# The_ghostLink_schematic.net
KiCad netlist of a schematic drawn in EasyEDA
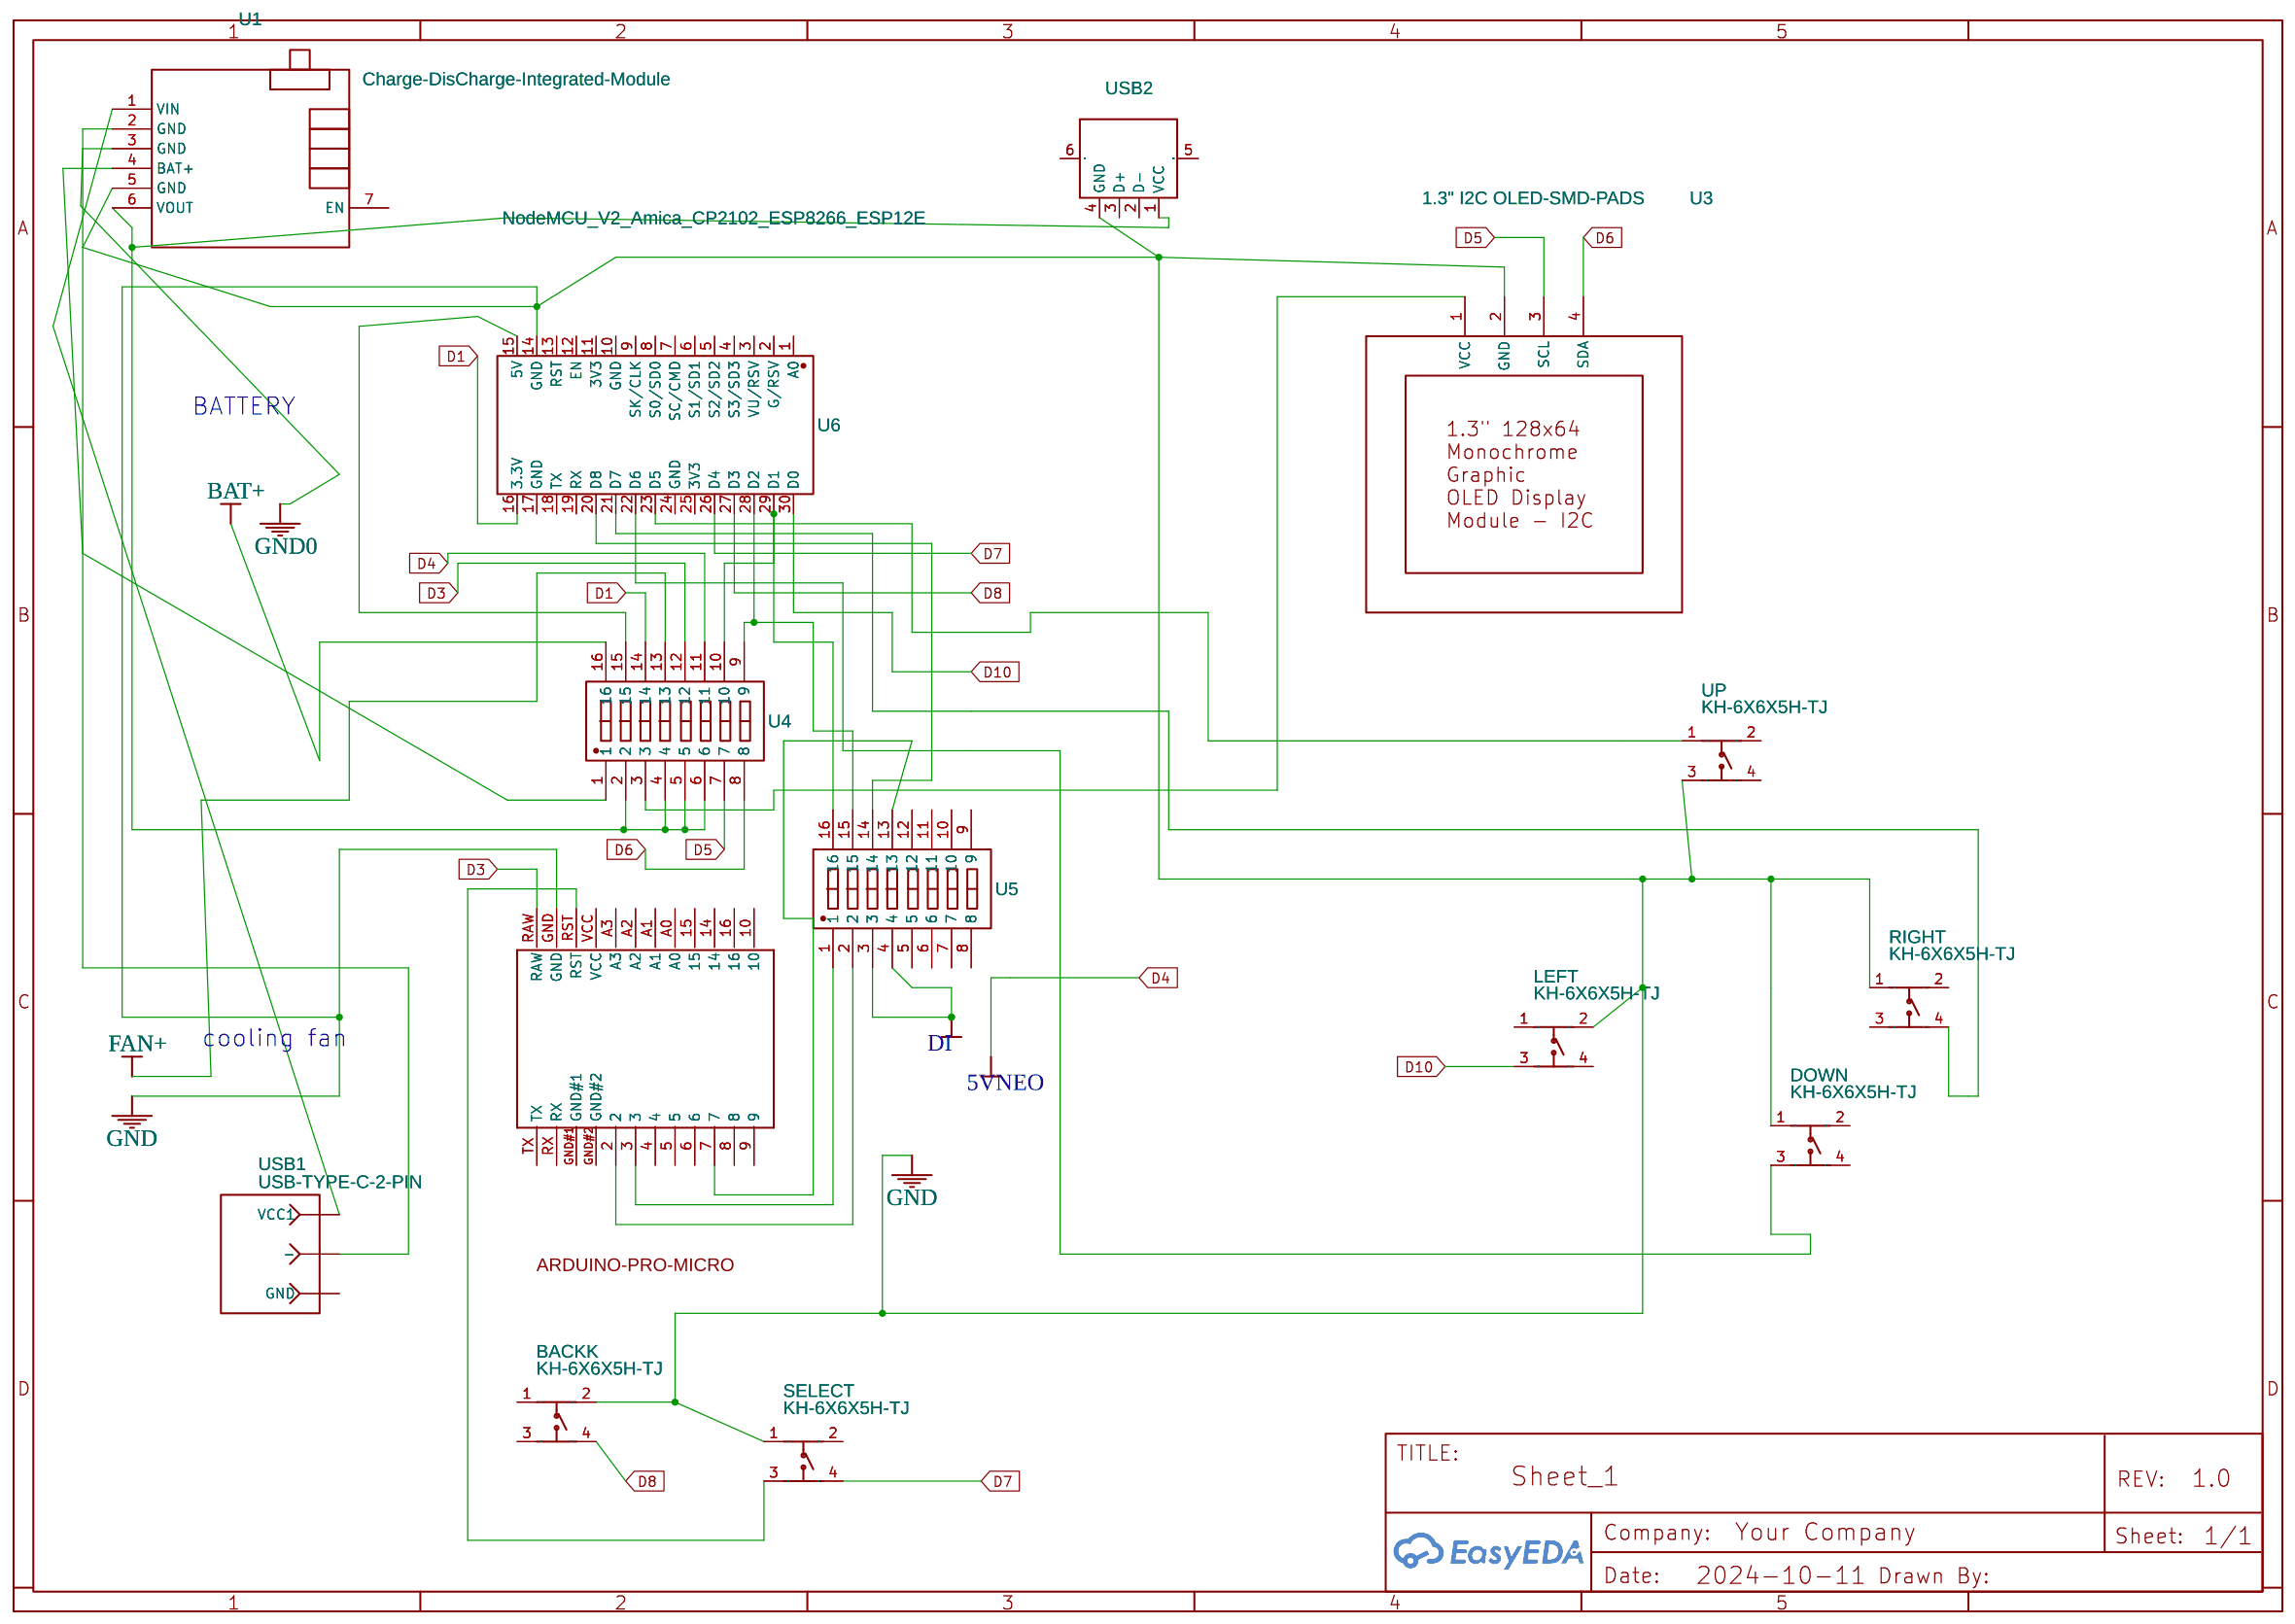
[diagram p0: schematic sheet]

(export (version "E")
  (design (tool "Eeschema 10.0.6"))
  (components
    (comp (ref "BACKK")
      (value "KH-6X6X5H-TJ")
      (fields (field (name "Manufacturer") "kinghelm(金航标)"))
      (libsource (lib "") (part "KH-6X6X5H-TJ_2"))
    )
    (comp (ref "DOWN")
      (value "KH-6X6X5H-TJ")
      (fields (field (name "Manufacturer") "kinghelm(金航标)"))
      (libsource (lib "") (part "KH-6X6X5H-TJ_1"))
    )
    (comp (ref "LEFT")
      (value "KH-6X6X5H-TJ")
      (fields (field (name "Manufacturer") "kinghelm(金航标)"))
      (libsource (lib "") (part "KH-6X6X5H-TJ"))
    )
    (comp (ref "RIGHT")
      (value "KH-6X6X5H-TJ")
      (fields (field (name "Manufacturer") "kinghelm(金航标)"))
      (libsource (lib "") (part "KH-6X6X5H-TJ_3"))
    )
    (comp (ref "SELECT")
      (value "KH-6X6X5H-TJ")
      (fields (field (name "Manufacturer") "kinghelm(金航标)"))
      (libsource (lib "") (part "KH-6X6X5H-TJ_4"))
    )
    (comp (ref "U1")
      (value "Charge-DisCharge-Integrated-Module")
      (libsource (lib "") (part "Charge-DisCharge-Integrated-Module"))
    )
    (comp (ref "U2") (value "ARDUINO PRO MICRO") (libsource (lib "") (part "ARDUINO PRO MICRO")))
    (comp (ref "U3")
      (value "1.3\" I2C OLED-SMD-PADS")
      (libsource (lib "") (part "1.3{dblquote} I2C OLED-SMD-PADS"))
    )
    (comp (ref "U4")
      (value "SMQS-08R-TP")
      (fields (field (name "Manufacturer") "SM Switch"))
      (libsource (lib "") (part "SMQS-08R-TP"))
    )
    (comp (ref "U5")
      (value "SMQS-08R-TP")
      (fields (field (name "Manufacturer") "SM Switch"))
      (libsource (lib "") (part "SMQS-08R-TP"))
    )
    (comp (ref "U6")
      (value "NodeMCU_V2_Amica_CP2102_ESP8266_ESP12E")
      (libsource (lib "") (part "NodeMCU_V2_Amica_CP2102_ESP8266_ESP12E"))
    )
    (comp (ref "UP")
      (value "KH-6X6X5H-TJ")
      (fields (field (name "Manufacturer") "kinghelm(金航标)"))
      (libsource (lib "") (part "KH-6X6X5H-TJ_5"))
    )
    (comp (ref "USB1") (value "USB-TYPE-C-2-PIN") (libsource (lib "") (part "USB-TYPE-C-2-PIN")))
    (comp (ref "USB2")
      (value "AF Bend foot Have side Inside the bomb iron PBT White plastic 90degree")
      (fields (field (name "Manufacturer Part") "901-131A1011D10100") (field (name "Manufacturer") "精拓金"))
      (libsource (lib "") (part "AF Bend foot Have side Inside the bomb iron PBT White plastic 90degree"))
    )
  )
  (nets
    (net (code "1") (name "BAT+") (class "Default")
      (node (ref "U4") (pin "16") (pinfunction "16_16") (pintype "unspecified"))
    )
    (net (code "2") (name "D1") (class "Default")
      (node (ref "U4") (pin "14") (pinfunction "14_14") (pintype "unspecified"))
      (node (ref "U6") (pin "16") (pinfunction "3.3V_16") (pintype "unspecified"))
    )
    (net (code "3") (name "D3") (class "Default")
      (node (ref "U2") (pin "RAW") (pinfunction "RAW_RAW") (pintype "bidirectional"))
      (node (ref "U4") (pin "12") (pinfunction "12_12") (pintype "unspecified"))
    )
    (net (code "4") (name "D4") (class "Default")
      (node (ref "U4") (pin "11") (pinfunction "11_11") (pintype "unspecified"))
    )
    (net (code "5") (name "D5") (class "Default")
      (node (ref "U3") (pin "3") (pinfunction "SCL_3") (pintype "unspecified"))
      (node (ref "U4") (pin "7") (pinfunction "7_7") (pintype "unspecified"))
    )
    (net (code "6") (name "D6") (class "Default")
      (node (ref "U3") (pin "4") (pinfunction "SDA_4") (pintype "unspecified"))
      (node (ref "U4") (pin "8") (pinfunction "8_8") (pintype "unspecified"))
    )
    (net (code "7") (name "D7") (class "Default")
      (node (ref "SELECT") (pin "4") (pinfunction "4_4") (pintype "unspecified"))
      (node (ref "U6") (pin "26") (pinfunction "D4_26") (pintype "unspecified"))
    )
    (net (code "8") (name "D8") (class "Default")
      (node (ref "BACKK") (pin "4") (pinfunction "4_4") (pintype "unspecified"))
      (node (ref "U6") (pin "27") (pinfunction "D3_27") (pintype "unspecified"))
    )
    (net (code "9") (name "D10") (class "Default")
      (node (ref "LEFT") (pin "3") (pinfunction "3_3") (pintype "unspecified"))
      (node (ref "U6") (pin "30") (pinfunction "D0_30") (pintype "unspecified"))
    )
    (net (code "10") (name "DI") (class "Default")
      (node (ref "U5") (pin "3") (pinfunction "3_3") (pintype "unspecified"))
      (node (ref "U5") (pin "4") (pinfunction "4_4") (pintype "unspecified"))
    )
    (net (code "11") (name "FAN+") (class "Default")
      (node (ref "U4") (pin "13") (pinfunction "13_13") (pintype "unspecified"))
    )
    (net (code "12") (name "GND") (class "Default")
      (node (ref "BACKK") (pin "2") (pinfunction "2_2") (pintype "unspecified"))
      (node (ref "DOWN") (pin "1") (pinfunction "1_1") (pintype "unspecified"))
      (node (ref "LEFT") (pin "2") (pinfunction "2_2") (pintype "unspecified"))
      (node (ref "RIGHT") (pin "1") (pinfunction "1_1") (pintype "unspecified"))
      (node (ref "SELECT") (pin "1") (pinfunction "1_1") (pintype "unspecified"))
      (node (ref "U1") (pin "5") (pinfunction "GND_5") (pintype "unspecified"))
      (node (ref "U2") (pin "GND") (pinfunction "GND_GND") (pintype "bidirectional"))
      (node (ref "U3") (pin "2") (pinfunction "GND_2") (pintype "unspecified"))
      (node (ref "U6") (pin "14") (pinfunction "GND_14") (pintype "unspecified"))
      (node (ref "UP") (pin "3") (pinfunction "3_3") (pintype "unspecified"))
      (node (ref "USB2") (pin "4") (pinfunction "GND_4") (pintype "input"))
    )
    (net (code "13") (name "GND0") (class "Default")
      (node (ref "U1") (pin "3") (pinfunction "GND_3") (pintype "unspecified"))
    )
    (net (code "14") (name "Net-(SELECT-Pad3)") (class "Default")
      (node (ref "SELECT") (pin "3") (pinfunction "3_3") (pintype "unspecified"))
      (node (ref "U2") (pin "RST") (pinfunction "RST_RST") (pintype "bidirectional"))
    )
    (net (code "15") (name "Net-(U1-BAT+)") (class "Default")
      (node (ref "U1") (pin "4") (pinfunction "BAT+_4") (pintype "unspecified"))
      (node (ref "U4") (pin "1") (pinfunction "1_1") (pintype "unspecified"))
    )
    (net (code "16") (name "Net-(U1-VIN)") (class "Default")
      (node (ref "U1") (pin "1") (pinfunction "VIN_1") (pintype "unspecified"))
      (node (ref "USB1") (pin "1") (pinfunction "VCC1_1") (pintype "unspecified"))
    )
    (net (code "17") (name "Net-(U1-VOUT)") (class "Default")
      (node (ref "U1") (pin "6") (pinfunction "VOUT_6") (pintype "unspecified"))
      (node (ref "U4") (pin "2") (pinfunction "2_2") (pintype "unspecified"))
      (node (ref "U4") (pin "4") (pinfunction "4_4") (pintype "unspecified"))
      (node (ref "U4") (pin "5") (pinfunction "5_5") (pintype "unspecified"))
      (node (ref "U4") (pin "6") (pinfunction "6_6") (pintype "unspecified"))
      (node (ref "USB2") (pin "1") (pinfunction "VCC_1") (pintype "input"))
    )
    (net (code "18") (name "Net-(U2-Pad2)") (class "Default")
      (node (ref "U2") (pin "2") (pinfunction "2_2") (pintype "bidirectional"))
      (node (ref "U5") (pin "2") (pinfunction "2_2") (pintype "unspecified"))
    )
    (net (code "19") (name "Net-(U2-Pad3)") (class "Default")
      (node (ref "U2") (pin "3") (pinfunction "3_3") (pintype "bidirectional"))
      (node (ref "U5") (pin "1") (pinfunction "1_1") (pintype "unspecified"))
    )
    (net (code "20") (name "Net-(U2-Pad7)") (class "Default")
      (node (ref "U2") (pin "7") (pinfunction "7_7") (pintype "bidirectional"))
      (node (ref "U5") (pin "13") (pinfunction "13_13") (pintype "unspecified"))
    )
    (net (code "21") (name "Net-(U3-VCC)") (class "Default")
      (node (ref "U3") (pin "1") (pinfunction "VCC_1") (pintype "unspecified"))
      (node (ref "U4") (pin "3") (pinfunction "3_3") (pintype "unspecified"))
    )
    (net (code "22") (name "Net-(U6-5V)") (class "Default")
      (node (ref "U4") (pin "15") (pinfunction "15_15") (pintype "unspecified"))
      (node (ref "U6") (pin "15") (pinfunction "5V_15") (pintype "unspecified"))
    )
    (net (code "23") (name "Net-(U6-D1)") (class "Default")
      (node (ref "U4") (pin "10") (pinfunction "10_10") (pintype "unspecified"))
      (node (ref "U5") (pin "16") (pinfunction "16_16") (pintype "unspecified"))
      (node (ref "U6") (pin "29") (pinfunction "D1_29") (pintype "unspecified"))
    )
    (net (code "24") (name "Net-(U6-D2)") (class "Default")
      (node (ref "U4") (pin "9") (pinfunction "9_9") (pintype "unspecified"))
      (node (ref "U5") (pin "15") (pinfunction "15_15") (pintype "unspecified"))
      (node (ref "U6") (pin "28") (pinfunction "D2_28") (pintype "unspecified"))
    )
    (net (code "25") (name "Net-(U6-D5)") (class "Default")
      (node (ref "U6") (pin "23") (pinfunction "D5_23") (pintype "unspecified"))
      (node (ref "UP") (pin "1") (pinfunction "1_1") (pintype "unspecified"))
    )
    (net (code "26") (name "Net-(U6-D6)") (class "Default")
      (node (ref "DOWN") (pin "3") (pinfunction "3_3") (pintype "unspecified"))
      (node (ref "U6") (pin "22") (pinfunction "D6_22") (pintype "unspecified"))
    )
    (net (code "27") (name "Net-(U6-D7)") (class "Default")
      (node (ref "RIGHT") (pin "4") (pinfunction "4_4") (pintype "unspecified"))
      (node (ref "U6") (pin "21") (pinfunction "D7_21") (pintype "unspecified"))
    )
    (net (code "28") (name "Net-(U6-D8)") (class "Default")
      (node (ref "U5") (pin "14") (pinfunction "14_14") (pintype "unspecified"))
      (node (ref "U6") (pin "20") (pinfunction "D8_20") (pintype "unspecified"))
    )
    (net (code "29") (name "Net-(USB1--)") (class "Default")
      (node (ref "U1") (pin "2") (pinfunction "GND_2") (pintype "unspecified"))
      (node (ref "USB1") (pin "2") (pinfunction "-_2") (pintype "unspecified"))
    )
    (net (code "30") (name "unconnected-(BACKK-Pad1)") (class "Default")
      (node (ref "BACKK") (pin "1") (pinfunction "1_1") (pintype "unspecified"))
    )
    (net (code "31") (name "unconnected-(BACKK-Pad3)") (class "Default")
      (node (ref "BACKK") (pin "3") (pinfunction "3_3") (pintype "unspecified"))
    )
    (net (code "32") (name "unconnected-(DOWN-Pad2)") (class "Default")
      (node (ref "DOWN") (pin "2") (pinfunction "2_2") (pintype "unspecified"))
    )
    (net (code "33") (name "unconnected-(DOWN-Pad4)") (class "Default")
      (node (ref "DOWN") (pin "4") (pinfunction "4_4") (pintype "unspecified"))
    )
    (net (code "34") (name "unconnected-(LEFT-Pad1)") (class "Default")
      (node (ref "LEFT") (pin "1") (pinfunction "1_1") (pintype "unspecified"))
    )
    (net (code "35") (name "unconnected-(LEFT-Pad4)") (class "Default")
      (node (ref "LEFT") (pin "4") (pinfunction "4_4") (pintype "unspecified"))
    )
    (net (code "36") (name "unconnected-(RIGHT-Pad2)") (class "Default")
      (node (ref "RIGHT") (pin "2") (pinfunction "2_2") (pintype "unspecified"))
    )
    (net (code "37") (name "unconnected-(RIGHT-Pad3)") (class "Default")
      (node (ref "RIGHT") (pin "3") (pinfunction "3_3") (pintype "unspecified"))
    )
    (net (code "38") (name "unconnected-(SELECT-Pad2)") (class "Default")
      (node (ref "SELECT") (pin "2") (pinfunction "2_2") (pintype "unspecified"))
    )
    (net (code "39") (name "unconnected-(U1-EN-Pad7)") (class "Default")
      (node (ref "U1") (pin "7") (pinfunction "EN_7") (pintype "unspecified"))
    )
    (net (code "40") (name "unconnected-(U2-Pad4)") (class "Default")
      (node (ref "U2") (pin "4") (pinfunction "4_4") (pintype "bidirectional"))
    )
    (net (code "41") (name "unconnected-(U2-Pad5)") (class "Default")
      (node (ref "U2") (pin "5") (pinfunction "5_5") (pintype "bidirectional"))
    )
    (net (code "42") (name "unconnected-(U2-Pad6)") (class "Default")
      (node (ref "U2") (pin "6") (pinfunction "6_6") (pintype "bidirectional"))
    )
    (net (code "43") (name "unconnected-(U2-Pad8)") (class "Default")
      (node (ref "U2") (pin "8") (pinfunction "8_8") (pintype "bidirectional"))
    )
    (net (code "44") (name "unconnected-(U2-Pad9)") (class "Default")
      (node (ref "U2") (pin "9") (pinfunction "9_9") (pintype "bidirectional"))
    )
    (net (code "45") (name "unconnected-(U2-Pad10)") (class "Default")
      (node (ref "U2") (pin "10") (pinfunction "10_10") (pintype "bidirectional"))
    )
    (net (code "46") (name "unconnected-(U2-Pad14)") (class "Default")
      (node (ref "U2") (pin "14") (pinfunction "14_14") (pintype "bidirectional"))
    )
    (net (code "47") (name "unconnected-(U2-Pad15)") (class "Default")
      (node (ref "U2") (pin "15") (pinfunction "15_15") (pintype "bidirectional"))
    )
    (net (code "48") (name "unconnected-(U2-Pad16)") (class "Default")
      (node (ref "U2") (pin "16") (pinfunction "16_16") (pintype "bidirectional"))
    )
    (net (code "49") (name "unconnected-(U2-PadA0)") (class "Default")
      (node (ref "U2") (pin "A0") (pinfunction "A0_A0") (pintype "bidirectional"))
    )
    (net (code "50") (name "unconnected-(U2-PadA1)") (class "Default")
      (node (ref "U2") (pin "A1") (pinfunction "A1_A1") (pintype "bidirectional"))
    )
    (net (code "51") (name "unconnected-(U2-PadA2)") (class "Default")
      (node (ref "U2") (pin "A2") (pinfunction "A2_A2") (pintype "bidirectional"))
    )
    (net (code "52") (name "unconnected-(U2-PadA3)") (class "Default")
      (node (ref "U2") (pin "A3") (pinfunction "A3_A3") (pintype "bidirectional"))
    )
    (net (code "53") (name "unconnected-(U2-PadGND#1)") (class "Default")
      (node (ref "U2") (pin "GND#1") (pinfunction "GND#1_GND#1") (pintype "bidirectional"))
    )
    (net (code "54") (name "unconnected-(U2-PadGND#2)") (class "Default")
      (node (ref "U2") (pin "GND#2") (pinfunction "GND#2_GND#2") (pintype "bidirectional"))
    )
    (net (code "55") (name "unconnected-(U2-PadRX)") (class "Default")
      (node (ref "U2") (pin "RX") (pinfunction "RX_RX") (pintype "bidirectional"))
    )
    (net (code "56") (name "unconnected-(U2-PadTX)") (class "Default")
      (node (ref "U2") (pin "TX") (pinfunction "TX_TX") (pintype "bidirectional"))
    )
    (net (code "57") (name "unconnected-(U2-PadVCC)") (class "Default")
      (node (ref "U2") (pin "VCC") (pinfunction "VCC_VCC") (pintype "bidirectional"))
    )
    (net (code "58") (name "unconnected-(U5-Pad5)") (class "Default")
      (node (ref "U5") (pin "5") (pinfunction "5_5") (pintype "unspecified"))
    )
    (net (code "59") (name "unconnected-(U5-Pad6)") (class "Default")
      (node (ref "U5") (pin "6") (pinfunction "6_6") (pintype "unspecified"))
    )
    (net (code "60") (name "unconnected-(U5-Pad7)") (class "Default")
      (node (ref "U5") (pin "7") (pinfunction "7_7") (pintype "unspecified"))
    )
    (net (code "61") (name "unconnected-(U5-Pad8)") (class "Default")
      (node (ref "U5") (pin "8") (pinfunction "8_8") (pintype "unspecified"))
    )
    (net (code "62") (name "unconnected-(U5-Pad9)") (class "Default")
      (node (ref "U5") (pin "9") (pinfunction "9_9") (pintype "unspecified"))
    )
    (net (code "63") (name "unconnected-(U5-Pad10)") (class "Default")
      (node (ref "U5") (pin "10") (pinfunction "10_10") (pintype "unspecified"))
    )
    (net (code "64") (name "unconnected-(U5-Pad11)") (class "Default")
      (node (ref "U5") (pin "11") (pinfunction "11_11") (pintype "unspecified"))
    )
    (net (code "65") (name "unconnected-(U5-Pad12)") (class "Default")
      (node (ref "U5") (pin "12") (pinfunction "12_12") (pintype "unspecified"))
    )
    (net (code "66") (name "unconnected-(U6-3V3-Pad11)") (class "Default")
      (node (ref "U6") (pin "11") (pinfunction "3V3_11") (pintype "unspecified"))
    )
    (net (code "67") (name "unconnected-(U6-3V3-Pad25)") (class "Default")
      (node (ref "U6") (pin "25") (pinfunction "3V3_25") (pintype "unspecified"))
    )
    (net (code "68") (name "unconnected-(U6-A0-Pad1)") (class "Default")
      (node (ref "U6") (pin "1") (pinfunction "A0_1") (pintype "unspecified"))
    )
    (net (code "69") (name "unconnected-(U6-EN-Pad12)") (class "Default")
      (node (ref "U6") (pin "12") (pinfunction "EN_12") (pintype "unspecified"))
    )
    (net (code "70") (name "unconnected-(U6-GND-Pad10)") (class "Default")
      (node (ref "U6") (pin "10") (pinfunction "GND_10") (pintype "unspecified"))
    )
    (net (code "71") (name "unconnected-(U6-GND-Pad17)") (class "Default")
      (node (ref "U6") (pin "17") (pinfunction "GND_17") (pintype "unspecified"))
    )
    (net (code "72") (name "unconnected-(U6-GND-Pad24)") (class "Default")
      (node (ref "U6") (pin "24") (pinfunction "GND_24") (pintype "unspecified"))
    )
    (net (code "73") (name "unconnected-(U6-G{slash}RSV-Pad2)") (class "Default")
      (node (ref "U6") (pin "2") (pinfunction "G/RSV_2") (pintype "unspecified"))
    )
    (net (code "74") (name "unconnected-(U6-RST-Pad13)") (class "Default")
      (node (ref "U6") (pin "13") (pinfunction "RST_13") (pintype "unspecified"))
    )
    (net (code "75") (name "unconnected-(U6-RX-Pad19)") (class "Default")
      (node (ref "U6") (pin "19") (pinfunction "RX_19") (pintype "unspecified"))
    )
    (net (code "76") (name "unconnected-(U6-S0{slash}SD0-Pad8)") (class "Default")
      (node (ref "U6") (pin "8") (pinfunction "S0/SD0_8") (pintype "unspecified"))
    )
    (net (code "77") (name "unconnected-(U6-S1{slash}SD1-Pad6)") (class "Default")
      (node (ref "U6") (pin "6") (pinfunction "S1/SD1_6") (pintype "unspecified"))
    )
    (net (code "78") (name "unconnected-(U6-S2{slash}SD2-Pad5)") (class "Default")
      (node (ref "U6") (pin "5") (pinfunction "S2/SD2_5") (pintype "unspecified"))
    )
    (net (code "79") (name "unconnected-(U6-S3{slash}SD3-Pad4)") (class "Default")
      (node (ref "U6") (pin "4") (pinfunction "S3/SD3_4") (pintype "unspecified"))
    )
    (net (code "80") (name "unconnected-(U6-SC{slash}CMD-Pad7)") (class "Default")
      (node (ref "U6") (pin "7") (pinfunction "SC/CMD_7") (pintype "unspecified"))
    )
    (net (code "81") (name "unconnected-(U6-SK{slash}CLK-Pad9)") (class "Default")
      (node (ref "U6") (pin "9") (pinfunction "SK/CLK_9") (pintype "unspecified"))
    )
    (net (code "82") (name "unconnected-(U6-TX-Pad18)") (class "Default")
      (node (ref "U6") (pin "18") (pinfunction "TX_18") (pintype "unspecified"))
    )
    (net (code "83") (name "unconnected-(U6-VU{slash}RSV-Pad3)") (class "Default")
      (node (ref "U6") (pin "3") (pinfunction "VU/RSV_3") (pintype "unspecified"))
    )
    (net (code "84") (name "unconnected-(UP-Pad2)") (class "Default")
      (node (ref "UP") (pin "2") (pinfunction "2_2") (pintype "unspecified"))
    )
    (net (code "85") (name "unconnected-(UP-Pad4)") (class "Default")
      (node (ref "UP") (pin "4") (pinfunction "4_4") (pintype "unspecified"))
    )
    (net (code "86") (name "unconnected-(USB1-GND-Pad3)") (class "Default")
      (node (ref "USB1") (pin "3") (pinfunction "GND_3") (pintype "unspecified"))
    )
    (net (code "87") (name "unconnected-(USB2-D+-Pad3)") (class "Default")
      (node (ref "USB2") (pin "3") (pinfunction "D+_3") (pintype "input"))
    )
    (net (code "88") (name "unconnected-(USB2-D--Pad2)") (class "Default")
      (node (ref "USB2") (pin "2") (pinfunction "D-_2") (pintype "input"))
    )
    (net (code "89") (name "unconnected-(USB2-SH1-Pad6)") (class "Default")
      (node (ref "USB2") (pin "6") (pinfunction "SH1_6") (pintype "unspecified"))
    )
    (net (code "90") (name "unconnected-(USB2-SH2-Pad5)") (class "Default")
      (node (ref "USB2") (pin "5") (pinfunction "SH2_5") (pintype "unspecified"))
    )
  )
)
